# DS3231.net
KiCad netlist of a schematic drawn in Altium Designer
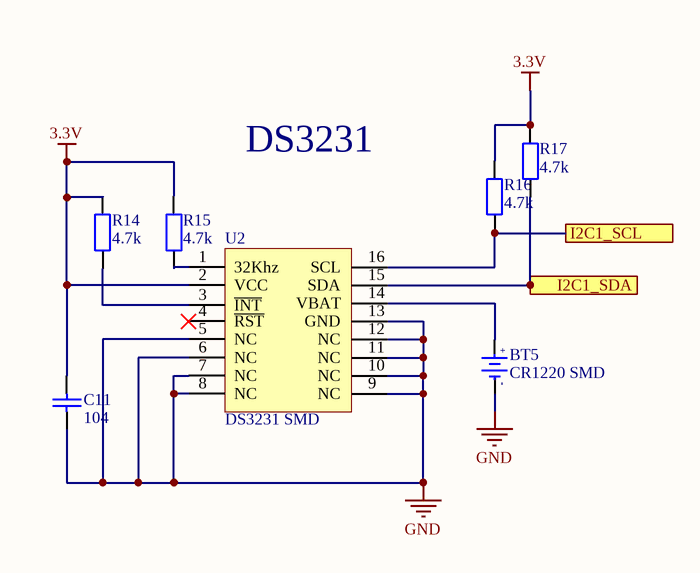
[diagram p0: DS3231.SchDoc]

(export (version "E")
  (design (tool "Eeschema 10.0.6"))
  (components
    (comp (ref "BT5")
      (value "CR1220 SMD")
      (footprint "DE PIN CR1220")
      (libsource (lib "Altium_Lib_by_KhueNguyenCreator") (part "De pin CR1220 SMD"))
    )
    (comp (ref "C11")
      (value "104")
      (footprint "tu 1206")
      (description "Dán")
      (libsource (lib "Altium_Lib_by_KhueNguyenCreator") (part "Tu 1206 104 50V 20%"))
    )
    (comp (ref "R14")
      (value "4.7k")
      (footprint "tro smd 0805")
      (description "Dán")
      (libsource (lib "Altium_Lib_by_KhueNguyenCreator") (part "Tro 0805 5% 4.7k"))
    )
    (comp (ref "R15")
      (value "4.7k")
      (footprint "tro smd 0805")
      (description "Dán")
      (libsource (lib "Altium_Lib_by_KhueNguyenCreator") (part "Tro 0805 5% 4.7k"))
    )
    (comp (ref "R16")
      (value "4.7k")
      (footprint "tro smd 0805")
      (description "Dán")
      (libsource (lib "Altium_Lib_by_KhueNguyenCreator") (part "Tro 0805 5% 4.7k"))
    )
    (comp (ref "R17")
      (value "4.7k")
      (footprint "tro smd 0805")
      (description "Dán")
      (libsource (lib "Altium_Lib_by_KhueNguyenCreator") (part "Tro 0805 5% 4.7k"))
    )
    (comp (ref "U2")
      (value "DS3231 SMD")
      (footprint "SOIC 16")
      (description "SOIC")
      (libsource (lib "Altium_Lib_by_KhueNguyenCreator") (part "DS3231 SMD"))
    )
  )
  (nets
    (net (code "1") (name "/I2C1_SCL") (class "Default")
      (node (ref "R16") (pin "1") (pinfunction "1_1") (pintype "passive"))
      (node (ref "U2") (pin "16") (pinfunction "SCL_16") (pintype "power_in"))
    )
    (net (code "2") (name "/I2C1_SDA") (class "Default")
      (node (ref "R17") (pin "1") (pinfunction "1_1") (pintype "passive"))
      (node (ref "U2") (pin "15") (pinfunction "SDA_15") (pintype "power_in"))
    )
    (net (code "3") (name "3.3V") (class "Default")
      (node (ref "C11") (pin "1") (pinfunction "1_1") (pintype "passive"))
      (node (ref "R14") (pin "2") (pinfunction "2_2") (pintype "passive"))
      (node (ref "R15") (pin "2") (pinfunction "2_2") (pintype "passive"))
      (node (ref "R16") (pin "2") (pinfunction "2_2") (pintype "passive"))
      (node (ref "R17") (pin "2") (pinfunction "2_2") (pintype "passive"))
      (node (ref "U2") (pin "2") (pinfunction "VCC_2") (pintype "power_in"))
    )
    (net (code "4") (name "GND") (class "Default")
      (node (ref "BT5") (pin "2") (pinfunction "GND_2") (pintype "passive"))
      (node (ref "C11") (pin "2") (pinfunction "2_2") (pintype "passive"))
      (node (ref "U2") (pin "10") (pinfunction "NC_10") (pintype "power_in"))
      (node (ref "U2") (pin "11") (pinfunction "NC_11") (pintype "power_in"))
      (node (ref "U2") (pin "12") (pinfunction "NC_12") (pintype "power_in"))
      (node (ref "U2") (pin "13") (pinfunction "GND_13") (pintype "power_in"))
      (node (ref "U2") (pin "5") (pinfunction "NC_5") (pintype "power_in"))
      (node (ref "U2") (pin "6") (pinfunction "NC_6") (pintype "power_in"))
      (node (ref "U2") (pin "7") (pinfunction "NC_7") (pintype "power_in"))
      (node (ref "U2") (pin "8") (pinfunction "NC_8") (pintype "power_in"))
      (node (ref "U2") (pin "9") (pinfunction "NC_9") (pintype "power_in"))
    )
    (net (code "5") (name "Net-(BT5-+3V)") (class "Default")
      (node (ref "BT5") (pin "1") (pinfunction "+3V_1") (pintype "passive"))
      (node (ref "U2") (pin "14") (pinfunction "VBAT_14") (pintype "power_in"))
    )
    (net (code "6") (name "Net-(U2-32Khz)") (class "Default")
      (node (ref "R15") (pin "1") (pinfunction "1_1") (pintype "passive"))
      (node (ref "U2") (pin "1") (pinfunction "32Khz_1") (pintype "power_in"))
    )
    (net (code "7") (name "Net-(U2-~{INT})") (class "Default")
      (node (ref "R14") (pin "1") (pinfunction "1_1") (pintype "passive"))
      (node (ref "U2") (pin "3") (pinfunction "~{INT}_3") (pintype "power_in"))
    )
    (net (code "8") (name "unconnected-(U2-~{RST}-Pad4)") (class "Default")
      (node (ref "U2") (pin "4") (pinfunction "~{RST}_4") (pintype "power_in+no_connect"))
    )
  )
)
